# SI4844_LCD16x02_setup.net
KiCad netlist of a schematic drawn in EAGLE
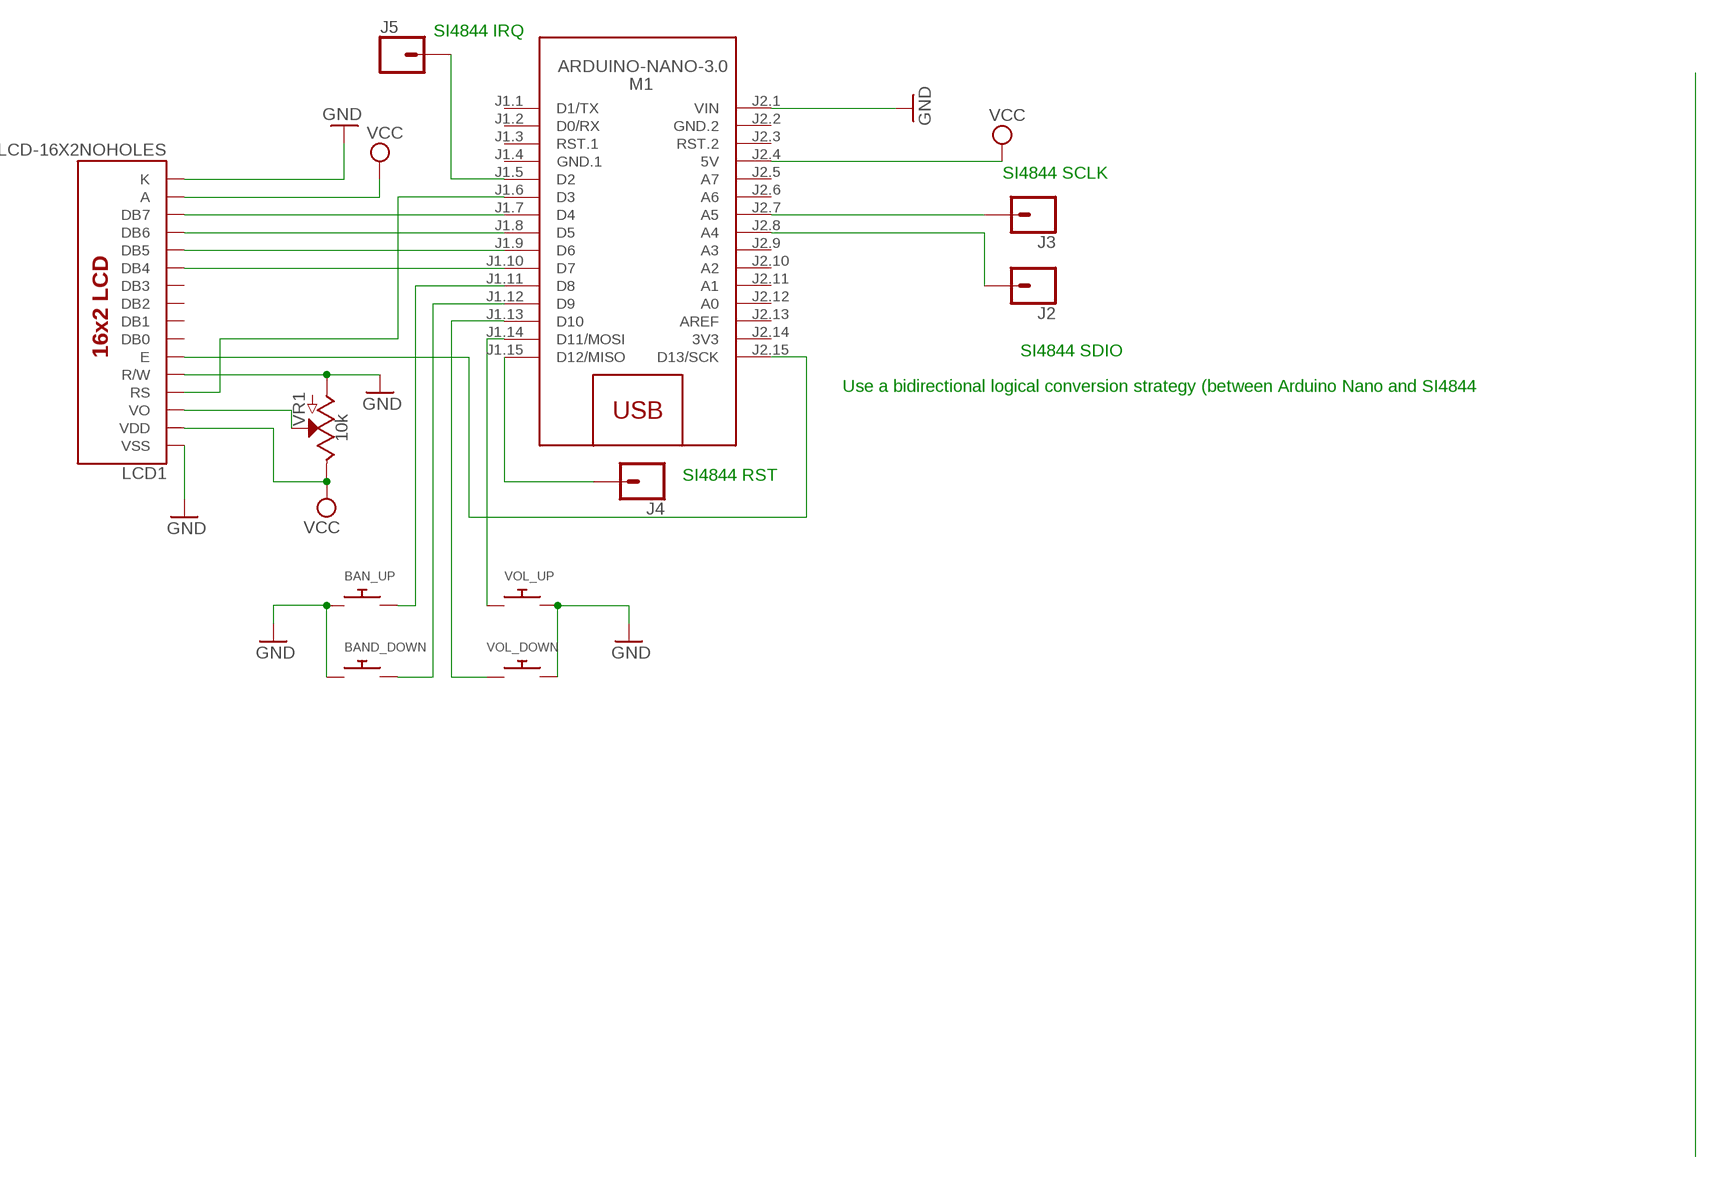
[diagram p0: schematic, sheet 1]

(export (version "E")
  (design (tool "Eeschema 10.0.6"))
  (components
    (comp (ref "BAND_DOWN")
      (value "SWITCH_PUSHBUTTONC&K_KSS")
      (footprint "eagle-import:BTN_CK_KSS")
      (libsource (lib "eagle-import") (part "SWITCH_PUSHBUTTONC&K_KSS"))
    )
    (comp (ref "BAN_UP")
      (value "SWITCH_PUSHBUTTONC&K_KSS")
      (footprint "eagle-import:BTN_CK_KSS")
      (libsource (lib "eagle-import") (part "SWITCH_PUSHBUTTONC&K_KSS"))
    )
    (comp (ref "J2")
      (value "CONN_01")
      (footprint "eagle-import:1X01")
      (libsource (lib "eagle-import") (part "CONN_01"))
    )
    (comp (ref "J3")
      (value "CONN_01")
      (footprint "eagle-import:1X01")
      (libsource (lib "eagle-import") (part "CONN_01"))
    )
    (comp (ref "J4")
      (value "CONN_01")
      (footprint "eagle-import:1X01")
      (libsource (lib "eagle-import") (part "CONN_01"))
    )
    (comp (ref "J5")
      (value "CONN_01")
      (footprint "eagle-import:1X01")
      (libsource (lib "eagle-import") (part "CONN_01"))
    )
    (comp (ref "LCD1")
      (value "LCD-16X2NOHOLES")
      (footprint "eagle-import:LCD-16X2_NOHOLESNOSILK")
      (libsource (lib "eagle-import") (part "LCD-16X2NOHOLES"))
    )
    (comp (ref "M1")
      (value "ARDUINO-NANO-3.0")
      (footprint "eagle-import:ARDUINO-NANO-3.0")
      (libsource (lib "eagle-import") (part "ARDUINO-NANO-3.0"))
    )
    (comp (ref "VOL_DOWN")
      (value "SWITCH_PUSHBUTTONC&K_KSS")
      (footprint "eagle-import:BTN_CK_KSS")
      (libsource (lib "eagle-import") (part "SWITCH_PUSHBUTTONC&K_KSS"))
    )
    (comp (ref "VOL_UP")
      (value "SWITCH_PUSHBUTTONC&K_KSS")
      (footprint "eagle-import:BTN_CK_KSS")
      (libsource (lib "eagle-import") (part "SWITCH_PUSHBUTTONC&K_KSS"))
    )
    (comp (ref "VR1")
      (value "10k")
      (footprint "eagle-import:POT-PTH-ALPS")
      (libsource (lib "eagle-import") (part "POTENTIOMETER-PTH-9MM-1/20W-20%"))
    )
  )
  (nets
    (net (code "1") (name "/3V3") (class "Default")
      (node (ref "M1") (pin "J2.14") (pinfunction "3V3_J2.14") (pintype "power_in"))
    )
    (net (code "2") (name "/GND.1") (class "Default")
      (node (ref "M1") (pin "J1.4") (pinfunction "GND.1_J1.4") (pintype "power_in"))
    )
    (net (code "3") (name "/GND.2") (class "Default")
      (node (ref "M1") (pin "J2.2") (pinfunction "GND.2_J2.2") (pintype "power_in"))
    )
    (net (code "4") (name "GND") (class "Default")
      (node (ref "BAND_DOWN") (pin "P$1") (pinfunction "P$1_P$1") (pintype "passive"))
      (node (ref "BAN_UP") (pin "P$1") (pinfunction "P$1_P$1") (pintype "passive"))
      (node (ref "LCD1") (pin "1") (pinfunction "VSS_1") (pintype "power_in"))
      (node (ref "LCD1") (pin "16") (pinfunction "K_16") (pintype "power_in"))
      (node (ref "LCD1") (pin "5") (pinfunction "R/W_5") (pintype "input"))
      (node (ref "M1") (pin "J2.1") (pinfunction "VIN_J2.1") (pintype "power_in"))
      (node (ref "VOL_DOWN") (pin "P$2") (pinfunction "P$2_P$2") (pintype "passive"))
      (node (ref "VOL_UP") (pin "P$2") (pinfunction "P$2_P$2") (pintype "passive"))
      (node (ref "VR1") (pin "P$3") (pinfunction "A_P$3") (pintype "passive"))
    )
    (net (code "5") (name "Net-(LCD1-DB4)") (class "Default")
      (node (ref "LCD1") (pin "11") (pinfunction "DB4_11") (pintype "bidirectional"))
      (node (ref "M1") (pin "J1.10") (pinfunction "D7_J1.10") (pintype "bidirectional"))
    )
    (net (code "6") (name "Net-(LCD1-DB5)") (class "Default")
      (node (ref "LCD1") (pin "12") (pinfunction "DB5_12") (pintype "bidirectional"))
      (node (ref "M1") (pin "J1.9") (pinfunction "D6_J1.9") (pintype "bidirectional"))
    )
    (net (code "7") (name "Net-(LCD1-DB6)") (class "Default")
      (node (ref "LCD1") (pin "13") (pinfunction "DB6_13") (pintype "bidirectional"))
      (node (ref "M1") (pin "J1.8") (pinfunction "D5_J1.8") (pintype "bidirectional"))
    )
    (net (code "8") (name "Net-(LCD1-DB7)") (class "Default")
      (node (ref "LCD1") (pin "14") (pinfunction "DB7_14") (pintype "bidirectional"))
      (node (ref "M1") (pin "J1.7") (pinfunction "D4_J1.7") (pintype "bidirectional"))
    )
    (net (code "9") (name "Net-(LCD1-E)") (class "Default")
      (node (ref "LCD1") (pin "6") (pinfunction "E_6") (pintype "input"))
      (node (ref "M1") (pin "J2.15") (pinfunction "D13/SCK_J2.15") (pintype "bidirectional"))
    )
    (net (code "10") (name "Net-(LCD1-RS)") (class "Default")
      (node (ref "LCD1") (pin "4") (pinfunction "RS_4") (pintype "input"))
      (node (ref "M1") (pin "J1.6") (pinfunction "D3_J1.6") (pintype "bidirectional"))
    )
    (net (code "11") (name "Net-(LCD1-VO)") (class "Default")
      (node (ref "LCD1") (pin "3") (pinfunction "VO_3") (pintype "bidirectional"))
      (node (ref "VR1") (pin "P$2") (pinfunction "S_P$2") (pintype "passive"))
    )
    (net (code "12") (name "Net-(M1-A4)") (class "Default")
      (node (ref "J2") (pin "1") (pinfunction "1_1") (pintype "passive"))
      (node (ref "M1") (pin "J2.8") (pinfunction "A4_J2.8") (pintype "bidirectional"))
    )
    (net (code "13") (name "Net-(M1-A5)") (class "Default")
      (node (ref "J3") (pin "1") (pinfunction "1_1") (pintype "passive"))
      (node (ref "M1") (pin "J2.7") (pinfunction "A5_J2.7") (pintype "bidirectional"))
    )
    (net (code "14") (name "Net-(M1-D2)") (class "Default")
      (node (ref "J5") (pin "1") (pinfunction "1_1") (pintype "passive"))
      (node (ref "M1") (pin "J1.5") (pinfunction "D2_J1.5") (pintype "bidirectional"))
    )
    (net (code "15") (name "Net-(M1-D8)") (class "Default")
      (node (ref "BAN_UP") (pin "P$2") (pinfunction "P$2_P$2") (pintype "passive"))
      (node (ref "M1") (pin "J1.11") (pinfunction "D8_J1.11") (pintype "bidirectional"))
    )
    (net (code "16") (name "Net-(M1-D9)") (class "Default")
      (node (ref "BAND_DOWN") (pin "P$2") (pinfunction "P$2_P$2") (pintype "passive"))
      (node (ref "M1") (pin "J1.12") (pinfunction "D9_J1.12") (pintype "bidirectional"))
    )
    (net (code "17") (name "Net-(M1-D10)") (class "Default")
      (node (ref "M1") (pin "J1.13") (pinfunction "D10_J1.13") (pintype "bidirectional"))
      (node (ref "VOL_DOWN") (pin "P$1") (pinfunction "P$1_P$1") (pintype "passive"))
    )
    (net (code "18") (name "Net-(M1-D11{slash}MOSI)") (class "Default")
      (node (ref "M1") (pin "J1.14") (pinfunction "D11/MOSI_J1.14") (pintype "bidirectional"))
      (node (ref "VOL_UP") (pin "P$1") (pinfunction "P$1_P$1") (pintype "passive"))
    )
    (net (code "19") (name "Net-(M1-D12{slash}MISO)") (class "Default")
      (node (ref "J4") (pin "1") (pinfunction "1_1") (pintype "passive"))
      (node (ref "M1") (pin "J1.15") (pinfunction "D12/MISO_J1.15") (pintype "bidirectional"))
    )
    (net (code "20") (name "VCC") (class "Default")
      (node (ref "LCD1") (pin "15") (pinfunction "A_15") (pintype "power_in"))
      (node (ref "LCD1") (pin "2") (pinfunction "VDD_2") (pintype "power_in"))
      (node (ref "M1") (pin "J2.4") (pinfunction "5V_J2.4") (pintype "power_in"))
      (node (ref "VR1") (pin "P$1") (pinfunction "E_P$1") (pintype "passive"))
    )
    (net (code "21") (name "unconnected-(LCD1-DB0-Pad7)") (class "Default")
      (node (ref "LCD1") (pin "7") (pinfunction "DB0_7") (pintype "bidirectional"))
    )
    (net (code "22") (name "unconnected-(LCD1-DB1-Pad8)") (class "Default")
      (node (ref "LCD1") (pin "8") (pinfunction "DB1_8") (pintype "bidirectional"))
    )
    (net (code "23") (name "unconnected-(LCD1-DB2-Pad9)") (class "Default")
      (node (ref "LCD1") (pin "9") (pinfunction "DB2_9") (pintype "bidirectional"))
    )
    (net (code "24") (name "unconnected-(LCD1-DB3-Pad10)") (class "Default")
      (node (ref "LCD1") (pin "10") (pinfunction "DB3_10") (pintype "bidirectional"))
    )
    (net (code "25") (name "unconnected-(M1-A0-PadJ2.12)") (class "Default")
      (node (ref "M1") (pin "J2.12") (pinfunction "A0_J2.12") (pintype "bidirectional"))
    )
    (net (code "26") (name "unconnected-(M1-A1-PadJ2.11)") (class "Default")
      (node (ref "M1") (pin "J2.11") (pinfunction "A1_J2.11") (pintype "bidirectional"))
    )
    (net (code "27") (name "unconnected-(M1-A2-PadJ2.10)") (class "Default")
      (node (ref "M1") (pin "J2.10") (pinfunction "A2_J2.10") (pintype "bidirectional"))
    )
    (net (code "28") (name "unconnected-(M1-A3-PadJ2.9)") (class "Default")
      (node (ref "M1") (pin "J2.9") (pinfunction "A3_J2.9") (pintype "bidirectional"))
    )
    (net (code "29") (name "unconnected-(M1-A6-PadJ2.6)") (class "Default")
      (node (ref "M1") (pin "J2.6") (pinfunction "A6_J2.6") (pintype "bidirectional"))
    )
    (net (code "30") (name "unconnected-(M1-A7-PadJ2.5)") (class "Default")
      (node (ref "M1") (pin "J2.5") (pinfunction "A7_J2.5") (pintype "bidirectional"))
    )
    (net (code "31") (name "unconnected-(M1-AREF-PadJ2.13)") (class "Default")
      (node (ref "M1") (pin "J2.13") (pinfunction "AREF_J2.13") (pintype "bidirectional"))
    )
    (net (code "32") (name "unconnected-(M1-D0{slash}RX-PadJ1.2)") (class "Default")
      (node (ref "M1") (pin "J1.2") (pinfunction "D0/RX_J1.2") (pintype "bidirectional"))
    )
    (net (code "33") (name "unconnected-(M1-D1{slash}TX-PadJ1.1)") (class "Default")
      (node (ref "M1") (pin "J1.1") (pinfunction "D1/TX_J1.1") (pintype "bidirectional"))
    )
    (net (code "34") (name "unconnected-(M1-RST.1-PadJ1.3)") (class "Default")
      (node (ref "M1") (pin "J1.3") (pinfunction "RST.1_J1.3") (pintype "bidirectional"))
    )
    (net (code "35") (name "unconnected-(M1-RST.2-PadJ2.3)") (class "Default")
      (node (ref "M1") (pin "J2.3") (pinfunction "RST.2_J2.3") (pintype "bidirectional"))
    )
  )
)
